# uio_u.net
KiCad netlist of a schematic drawn in EAGLE
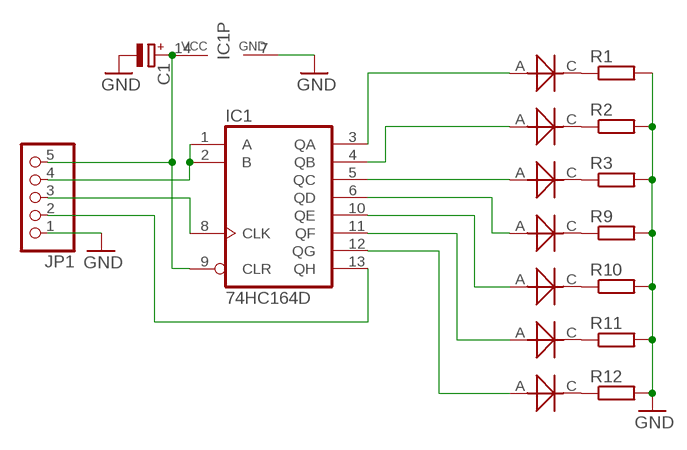
[diagram p0: schematic, sheet 1]

(export (version "E")
  (design (tool "Eeschema 10.0.6"))
  (components
    (comp (ref "C1")
      (value "CPOL-EUSMCA")
      (footprint "eagle-import:SMC_A")
      (libsource (lib "eagle-import") (part "CPOL-EUSMCA"))
    )
    (comp (ref "IC1")
      (value "74HC164D")
      (footprint "eagle-import:SO14")
      (libsource (lib "eagle-import") (part "74164DHC"))
    )
    (comp (ref "JP1")
      (value "PINHD-1X05_2.54-S")
      (footprint "eagle-import:1X05-S")
      (libsource (lib "eagle-import") (part "PINHD-1X05_2.54-S"))
    )
    (comp (ref "R1")
      (value "R_0805")
      (footprint "eagle-import:R0805")
      (libsource (lib "eagle-import") (part "R_0805"))
    )
    (comp (ref "R2")
      (value "R_0805")
      (footprint "eagle-import:R0805")
      (libsource (lib "eagle-import") (part "R_0805"))
    )
    (comp (ref "R3")
      (value "R_0805")
      (footprint "eagle-import:R0805")
      (libsource (lib "eagle-import") (part "R_0805"))
    )
    (comp (ref "R9")
      (value "R_0805")
      (footprint "eagle-import:R0805")
      (libsource (lib "eagle-import") (part "R_0805"))
    )
    (comp (ref "R10")
      (value "R_0805")
      (footprint "eagle-import:R0805")
      (libsource (lib "eagle-import") (part "R_0805"))
    )
    (comp (ref "R11")
      (value "R_0805")
      (footprint "eagle-import:R0805")
      (libsource (lib "eagle-import") (part "R_0805"))
    )
    (comp (ref "R12")
      (value "R_0805")
      (footprint "eagle-import:R0805")
      (libsource (lib "eagle-import") (part "R_0805"))
    )
    (comp (ref "U$1")
      (value "LED5X2")
      (footprint "eagle-import:LED_5X2")
      (libsource (lib "eagle-import") (part "LED5X2"))
    )
    (comp (ref "U$2")
      (value "LED5X2")
      (footprint "eagle-import:LED_5X2")
      (libsource (lib "eagle-import") (part "LED5X2"))
    )
    (comp (ref "U$3")
      (value "LED5X2")
      (footprint "eagle-import:LED_5X2")
      (libsource (lib "eagle-import") (part "LED5X2"))
    )
    (comp (ref "U$4")
      (value "LED5X2")
      (footprint "eagle-import:LED_5X2")
      (libsource (lib "eagle-import") (part "LED5X2"))
    )
    (comp (ref "U$11")
      (value "LED5X2")
      (footprint "eagle-import:LED_5X2")
      (libsource (lib "eagle-import") (part "LED5X2"))
    )
    (comp (ref "U$12")
      (value "LED5X2")
      (footprint "eagle-import:LED_5X2")
      (libsource (lib "eagle-import") (part "LED5X2"))
    )
    (comp (ref "U$13")
      (value "LED5X2")
      (footprint "eagle-import:LED_5X2")
      (libsource (lib "eagle-import") (part "LED5X2"))
    )
  )
  (nets
    (net (code "1") (name "GND") (class "Default")
      (node (ref "C1") (pin "-") (pinfunction "-_-") (pintype "passive"))
      (node (ref "IC1") (pin "7") (pinfunction "GND_7") (pintype "power_in"))
      (node (ref "JP1") (pin "1") (pinfunction "1_1") (pintype "passive"))
      (node (ref "R1") (pin "2") (pinfunction "2_2") (pintype "passive"))
      (node (ref "R10") (pin "2") (pinfunction "2_2") (pintype "passive"))
      (node (ref "R11") (pin "2") (pinfunction "2_2") (pintype "passive"))
      (node (ref "R12") (pin "2") (pinfunction "2_2") (pintype "passive"))
      (node (ref "R2") (pin "2") (pinfunction "2_2") (pintype "passive"))
      (node (ref "R3") (pin "2") (pinfunction "2_2") (pintype "passive"))
      (node (ref "R9") (pin "2") (pinfunction "2_2") (pintype "passive"))
    )
    (net (code "2") (name "Net-(IC1A-A)") (class "Default")
      (node (ref "IC1") (pin "1") (pinfunction "A_1") (pintype "input"))
      (node (ref "IC1") (pin "2") (pinfunction "B_2") (pintype "input"))
      (node (ref "JP1") (pin "4") (pinfunction "4_4") (pintype "passive"))
    )
    (net (code "3") (name "Net-(IC1A-CLK)") (class "Default")
      (node (ref "IC1") (pin "8") (pinfunction "CLK_8") (pintype "input"))
      (node (ref "JP1") (pin "3") (pinfunction "3_3") (pintype "passive"))
    )
    (net (code "4") (name "Net-(IC1A-CLR)") (class "Default")
      (node (ref "C1") (pin "+") (pinfunction "+_+") (pintype "passive"))
      (node (ref "IC1") (pin "14") (pinfunction "VCC_14") (pintype "power_in"))
      (node (ref "IC1") (pin "9") (pinfunction "CLR_9") (pintype "input"))
      (node (ref "JP1") (pin "5") (pinfunction "5_5") (pintype "passive"))
    )
    (net (code "5") (name "Net-(IC1A-QA)") (class "Default")
      (node (ref "IC1") (pin "3") (pinfunction "QA_3") (pintype "output"))
      (node (ref "U$4") (pin "A") (pinfunction "A_A") (pintype "bidirectional"))
    )
    (net (code "6") (name "Net-(IC1A-QB)") (class "Default")
      (node (ref "IC1") (pin "4") (pinfunction "QB_4") (pintype "output"))
      (node (ref "U$2") (pin "A") (pinfunction "A_A") (pintype "bidirectional"))
    )
    (net (code "7") (name "Net-(IC1A-QC)") (class "Default")
      (node (ref "IC1") (pin "5") (pinfunction "QC_5") (pintype "output"))
      (node (ref "U$3") (pin "A") (pinfunction "A_A") (pintype "bidirectional"))
    )
    (net (code "8") (name "Net-(IC1A-QD)") (class "Default")
      (node (ref "IC1") (pin "6") (pinfunction "QD_6") (pintype "output"))
      (node (ref "U$13") (pin "A") (pinfunction "A_A") (pintype "bidirectional"))
    )
    (net (code "9") (name "Net-(IC1A-QE)") (class "Default")
      (node (ref "IC1") (pin "10") (pinfunction "QE_10") (pintype "output"))
      (node (ref "U$1") (pin "A") (pinfunction "A_A") (pintype "bidirectional"))
    )
    (net (code "10") (name "Net-(IC1A-QF)") (class "Default")
      (node (ref "IC1") (pin "11") (pinfunction "QF_11") (pintype "output"))
      (node (ref "U$11") (pin "A") (pinfunction "A_A") (pintype "bidirectional"))
    )
    (net (code "11") (name "Net-(IC1A-QG)") (class "Default")
      (node (ref "IC1") (pin "12") (pinfunction "QG_12") (pintype "output"))
      (node (ref "U$12") (pin "A") (pinfunction "A_A") (pintype "bidirectional"))
    )
    (net (code "12") (name "Net-(IC1A-QH)") (class "Default")
      (node (ref "IC1") (pin "13") (pinfunction "QH_13") (pintype "output"))
      (node (ref "JP1") (pin "2") (pinfunction "2_2") (pintype "passive"))
    )
    (net (code "13") (name "Net-(R1-Pad1)") (class "Default")
      (node (ref "R1") (pin "1") (pinfunction "1_1") (pintype "passive"))
      (node (ref "U$4") (pin "C") (pinfunction "C_C") (pintype "bidirectional"))
    )
    (net (code "14") (name "Net-(R2-Pad1)") (class "Default")
      (node (ref "R2") (pin "1") (pinfunction "1_1") (pintype "passive"))
      (node (ref "U$2") (pin "C") (pinfunction "C_C") (pintype "bidirectional"))
    )
    (net (code "15") (name "Net-(R3-Pad1)") (class "Default")
      (node (ref "R3") (pin "1") (pinfunction "1_1") (pintype "passive"))
      (node (ref "U$3") (pin "C") (pinfunction "C_C") (pintype "bidirectional"))
    )
    (net (code "16") (name "Net-(R9-Pad1)") (class "Default")
      (node (ref "R9") (pin "1") (pinfunction "1_1") (pintype "passive"))
      (node (ref "U$13") (pin "C") (pinfunction "C_C") (pintype "bidirectional"))
    )
    (net (code "17") (name "Net-(R10-Pad1)") (class "Default")
      (node (ref "R10") (pin "1") (pinfunction "1_1") (pintype "passive"))
      (node (ref "U$1") (pin "C") (pinfunction "C_C") (pintype "bidirectional"))
    )
    (net (code "18") (name "Net-(R11-Pad1)") (class "Default")
      (node (ref "R11") (pin "1") (pinfunction "1_1") (pintype "passive"))
      (node (ref "U$11") (pin "C") (pinfunction "C_C") (pintype "bidirectional"))
    )
    (net (code "19") (name "Net-(R12-Pad1)") (class "Default")
      (node (ref "R12") (pin "1") (pinfunction "1_1") (pintype "passive"))
      (node (ref "U$12") (pin "C") (pinfunction "C_C") (pintype "bidirectional"))
    )
  )
)
